# EEP.net
KiCad netlist of a schematic drawn in Altium Designer
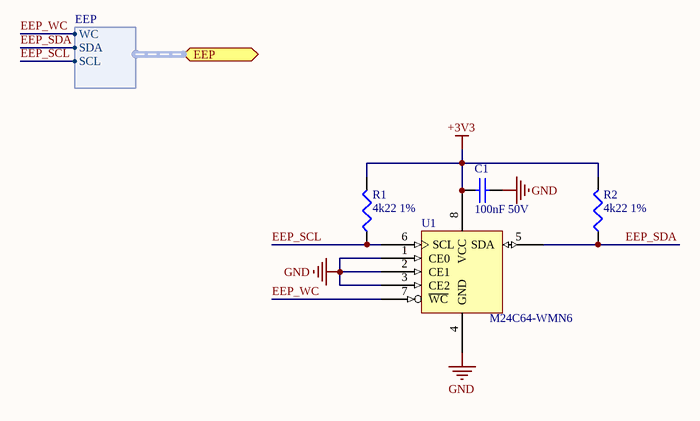
[diagram p0: EEP.SchDoc]

(export (version "E")
  (design (tool "Eeschema 10.0.6"))
  (components
    (comp (ref "C1")
      (value "100nF 50V")
      (footprint "IPC-7352 Chip_Capacitor_N:CAPC2012N")
      (description "Capacitor")
      (libsource (lib "*") (part "CAP"))
    )
    (comp (ref "R1")
      (value "4k22 1%")
      (footprint "IPC-7352 Chip_Resistor_N:RESC2012N")
      (description "Resistor")
      (fields (field (name "PUBLISHER") "Altium Limited"))
      (libsource (lib "Miscellaneous Devices") (part "Res3"))
    )
    (comp (ref "R2")
      (value "4k22 1%")
      (footprint "IPC-7352 Chip_Resistor_N:RESC2012N")
      (description "Resistor")
      (fields (field (name "PUBLISHER") "Altium Limited"))
      (libsource (lib "Miscellaneous Devices") (part "Res3"))
    )
    (comp (ref "U1")
      (value "M24C64-WMN6")
      (footprint "ST-Microelectronics Footprints:SO8_M")
      (description "Serial Extended Addressing Compatible With I2C Bus 64K(8K x 8) EEPROM")
      (fields (field (name "MANUFACTURER") "ST"))
      (libsource (lib "*") (part "ST24E64B6(8)"))
    )
  )
  (nets
    (net (code "2") (name "+3V3") (class "Default")
      (node (ref "C1") (pin "1") (pinfunction "1_1") (pintype "passive"))
      (node (ref "R1") (pin "2") (pinfunction "2_2") (pintype "passive"))
      (node (ref "R2") (pin "2") (pinfunction "2_2") (pintype "passive"))
      (node (ref "U1") (pin "8") (pinfunction "VCC_8") (pintype "power_in"))
    )
    (net (code "3") (name "/EEP_SCL") (class "Default")
      (node (ref "R1") (pin "1") (pinfunction "1_1") (pintype "passive"))
      (node (ref "U1") (pin "6") (pinfunction "SCL_6") (pintype "input"))
    )
    (net (code "4") (name "/EEP_SDA") (class "Default")
      (node (ref "R2") (pin "1") (pinfunction "1_1") (pintype "passive"))
      (node (ref "U1") (pin "5") (pinfunction "SDA_5") (pintype "bidirectional"))
    )
    (net (code "5") (name "/EEP_WC") (class "Default")
      (node (ref "U1") (pin "7") (pinfunction "~{WC}_7") (pintype "input"))
    )
    (net (code "7") (name "GND") (class "Default")
      (node (ref "C1") (pin "2") (pinfunction "2_2") (pintype "passive"))
      (node (ref "U1") (pin "1") (pinfunction "CE0_1") (pintype "input"))
      (node (ref "U1") (pin "2") (pinfunction "CE1_2") (pintype "input"))
      (node (ref "U1") (pin "3") (pinfunction "CE2_3") (pintype "input"))
      (node (ref "U1") (pin "4") (pinfunction "GND_4") (pintype "power_in"))
    )
  )
)
